# SparkFun_Air_Quality_ENS160.net
KiCad netlist of a schematic drawn in EAGLE
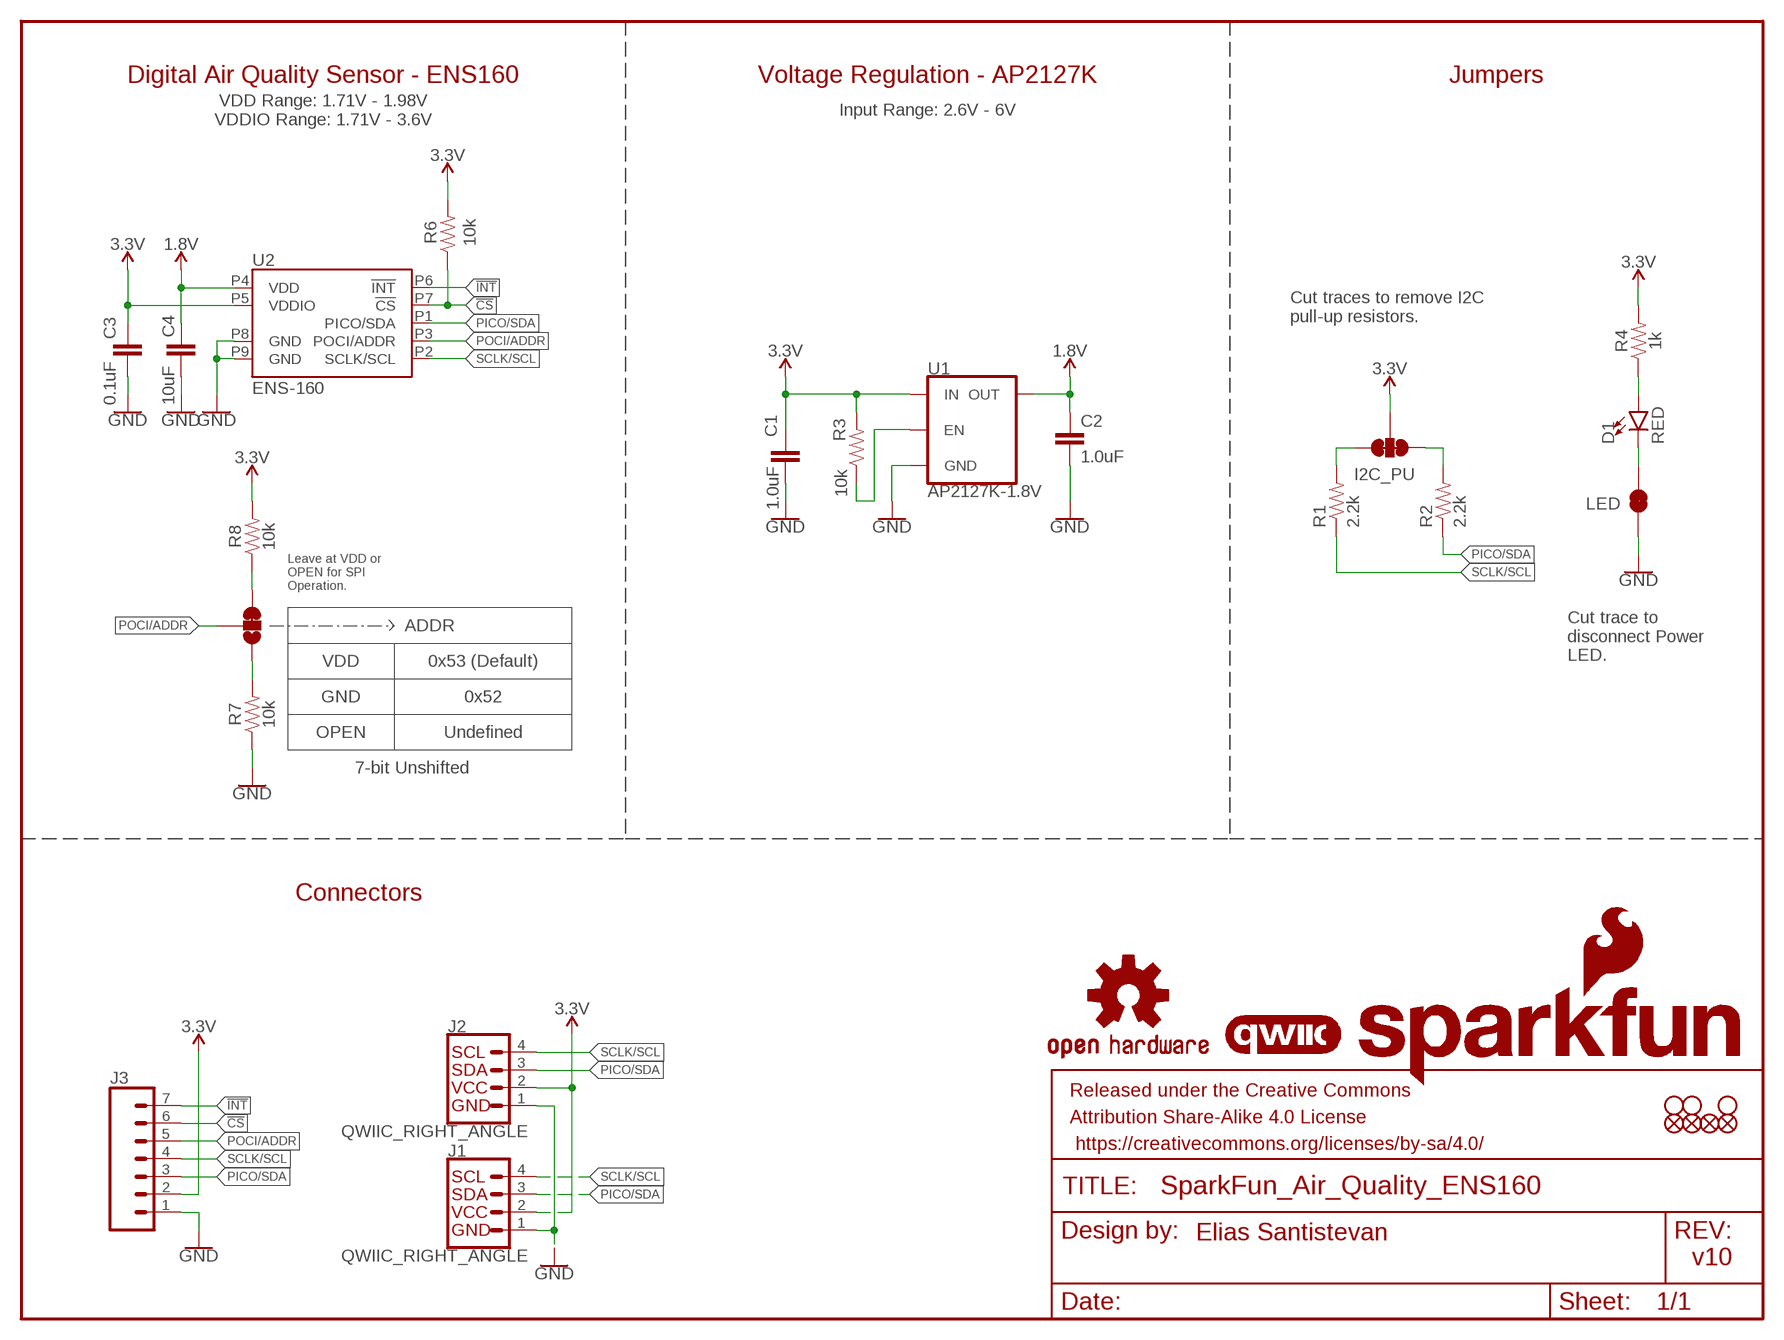
[diagram p0: schematic, sheet 1]

(export (version "E")
  (design (tool "Eeschema 10.0.6"))
  (components
    (comp (ref "ADDR")
      (value "JUMPER-SMT_3_1-NC_TRACE_SILK")
      (footprint "eagle-import:SMT-JUMPER_3_1-NC_TRACE_SILK")
      (libsource (lib "eagle-import") (part "JUMPER-SMT_3_1-NC_TRACE_SILK"))
    )
    (comp (ref "C1")
      (value "1.0uF")
      (footprint "eagle-import:0603")
      (libsource (lib "eagle-import") (part "1.0UF-0603-16V-10%"))
    )
    (comp (ref "C2")
      (value "1.0uF")
      (footprint "eagle-import:0603")
      (libsource (lib "eagle-import") (part "1.0UF-0603-16V-10%"))
    )
    (comp (ref "C3")
      (value "0.1uF")
      (footprint "eagle-import:0603")
      (libsource (lib "eagle-import") (part "0.1UF-0603-25V-(+80/-20%)"))
    )
    (comp (ref "C4")
      (value "10uF")
      (footprint "eagle-import:0603")
      (libsource (lib "eagle-import") (part "10UF-0603-6.3V-20%"))
    )
    (comp (ref "D1")
      (value "RED")
      (footprint "eagle-import:LED-0603")
      (libsource (lib "eagle-import") (part "LED-RED0603"))
    )
    (comp (ref "FD1")
      (value "FIDUCIAL1X2")
      (footprint "eagle-import:FIDUCIAL-1X2")
      (libsource (lib "eagle-import") (part "FIDUCIAL1X2"))
    )
    (comp (ref "FD2")
      (value "FIDUCIAL1X2")
      (footprint "eagle-import:FIDUCIAL-1X2")
      (libsource (lib "eagle-import") (part "FIDUCIAL1X2"))
    )
    (comp (ref "FD3")
      (value "FIDUCIAL1X2")
      (footprint "eagle-import:FIDUCIAL-1X2")
      (libsource (lib "eagle-import") (part "FIDUCIAL1X2"))
    )
    (comp (ref "FD4")
      (value "FIDUCIAL1X2")
      (footprint "eagle-import:FIDUCIAL-1X2")
      (libsource (lib "eagle-import") (part "FIDUCIAL1X2"))
    )
    (comp (ref "FRAME1")
      (value "FRAME-LETTER")
      (footprint "eagle-import:CREATIVE_COMMONS")
      (fields (field (name "DESIGNER") "Elias Santistevan"))
      (libsource (lib "eagle-import") (part "FRAME-LETTER"))
    )
    (comp (ref "I2C_PU")
      (value "S_MODE")
      (footprint "eagle-import:SMT-JUMPER_3_2-NC_TRACE_SILK")
      (libsource (lib "eagle-import") (part "JUMPER-SMT_3_2-NC_TRACE_SILK"))
    )
    (comp (ref "J1")
      (value "QWIIC_RIGHT_ANGLE")
      (footprint "eagle-import:JST04_1MM_RA")
      (libsource (lib "eagle-import") (part "QWIIC_CONNECTORJS-1MM"))
    )
    (comp (ref "J2")
      (value "QWIIC_RIGHT_ANGLE")
      (footprint "eagle-import:JST04_1MM_RA")
      (libsource (lib "eagle-import") (part "QWIIC_CONNECTORJS-1MM"))
    )
    (comp (ref "J3")
      (value "CONN_07NO_SILK")
      (footprint "eagle-import:1X07_NO_SILK")
      (libsource (lib "eagle-import") (part "CONN_07NO_SILK"))
    )
    (comp (ref "LED")
      (value "JUMPER-SMT_2_NC_TRACE_SILK")
      (footprint "eagle-import:SMT-JUMPER_2_NC_TRACE_SILK")
      (libsource (lib "eagle-import") (part "JUMPER-SMT_2_NC_TRACE_SILK"))
    )
    (comp (ref "LOGO2")
      (value "OSHW-LOGOMINI")
      (footprint "eagle-import:OSHW-LOGO-MINI")
      (libsource (lib "eagle-import") (part "OSHW-LOGOMINI"))
    )
    (comp (ref "LOGO3")
      (value "SFE_LOGO_NAME_FLAME.1_INCH")
      (footprint "eagle-import:SFE_LOGO_NAME_FLAME_.1")
      (libsource (lib "eagle-import") (part "SFE_LOGO_NAME_FLAME.1_INCH"))
    )
    (comp (ref "LOGO4")
      (value "QWIIC_LOGO_4MM")
      (footprint "eagle-import:QWIIC_4MM")
      (libsource (lib "eagle-import") (part "QWIIC_LOGO_4MM"))
    )
    (comp (ref "R1")
      (value "2.2k")
      (footprint "eagle-import:0603")
      (libsource (lib "eagle-import") (part "2.2KOHM-0603-1/10W-1%"))
    )
    (comp (ref "R2")
      (value "2.2k")
      (footprint "eagle-import:0603")
      (libsource (lib "eagle-import") (part "2.2KOHM-0603-1/10W-1%"))
    )
    (comp (ref "R3")
      (value "10k")
      (footprint "eagle-import:0603")
      (libsource (lib "eagle-import") (part "10KOHM-0603-1/10W-1%"))
    )
    (comp (ref "R4")
      (value "1k")
      (footprint "eagle-import:0603")
      (libsource (lib "eagle-import") (part "1KOHM-0603-1/10W-1%"))
    )
    (comp (ref "R6")
      (value "10k")
      (footprint "eagle-import:0603")
      (libsource (lib "eagle-import") (part "10KOHM-0603-1/10W-1%"))
    )
    (comp (ref "R7")
      (value "10k")
      (footprint "eagle-import:0603")
      (libsource (lib "eagle-import") (part "10KOHM-0603-1/10W-1%"))
    )
    (comp (ref "R8")
      (value "10k")
      (footprint "eagle-import:0603")
      (libsource (lib "eagle-import") (part "10KOHM-0603-1/10W-1%"))
    )
    (comp (ref "STANDOFF1")
      (value "STAND-OFFTIGHT")
      (footprint "eagle-import:STAND-OFF-TIGHT")
      (libsource (lib "eagle-import") (part "STAND-OFFTIGHT"))
    )
    (comp (ref "STANDOFF2")
      (value "STAND-OFFTIGHT")
      (footprint "eagle-import:STAND-OFF-TIGHT")
      (libsource (lib "eagle-import") (part "STAND-OFFTIGHT"))
    )
    (comp (ref "STANDOFF5")
      (value "STAND-OFFTIGHT")
      (footprint "eagle-import:STAND-OFF-TIGHT")
      (libsource (lib "eagle-import") (part "STAND-OFFTIGHT"))
    )
    (comp (ref "U1")
      (value "AP2127K-1.8V")
      (footprint "eagle-import:SOT23-5")
      (libsource (lib "eagle-import") (part "V_REG_AP2127K-1.8V"))
    )
    (comp (ref "U2")
      (value "ENS-160")
      (footprint "eagle-import:LGA-9")
      (libsource (lib "eagle-import") (part "ENS-160"))
    )
  )
  (nets
    (net (code "1") (name "/~{CS}") (class "Default")
      (node (ref "J3") (pin "6") (pinfunction "6_6") (pintype "passive"))
      (node (ref "R6") (pin "1") (pinfunction "1_1") (pintype "passive"))
      (node (ref "U2") (pin "P7") (pinfunction "~{CS}_P7") (pintype "bidirectional"))
    )
    (net (code "2") (name "/~{INT}") (class "Default")
      (node (ref "J3") (pin "7") (pinfunction "7_7") (pintype "passive"))
      (node (ref "U2") (pin "P6") (pinfunction "~{INT}_P6") (pintype "bidirectional"))
    )
    (net (code "3") (name "1.8V") (class "Default")
      (node (ref "C2") (pin "1") (pinfunction "1_1") (pintype "passive"))
      (node (ref "C4") (pin "1") (pinfunction "1_1") (pintype "passive"))
      (node (ref "U1") (pin "5") (pinfunction "OUT_5") (pintype "passive"))
      (node (ref "U2") (pin "P4") (pinfunction "VDD_P4") (pintype "power_in"))
    )
    (net (code "4") (name "3.3V") (class "Default")
      (node (ref "C1") (pin "1") (pinfunction "1_1") (pintype "passive"))
      (node (ref "C3") (pin "1") (pinfunction "1_1") (pintype "passive"))
      (node (ref "I2C_PU") (pin "2") (pinfunction "2_2") (pintype "passive"))
      (node (ref "J1") (pin "2") (pinfunction "2_2") (pintype "power_in"))
      (node (ref "J2") (pin "2") (pinfunction "2_2") (pintype "power_in"))
      (node (ref "J3") (pin "2") (pinfunction "2_2") (pintype "passive"))
      (node (ref "R3") (pin "2") (pinfunction "2_2") (pintype "passive"))
      (node (ref "R4") (pin "2") (pinfunction "2_2") (pintype "passive"))
      (node (ref "R6") (pin "2") (pinfunction "2_2") (pintype "passive"))
      (node (ref "R8") (pin "2") (pinfunction "2_2") (pintype "passive"))
      (node (ref "U1") (pin "1") (pinfunction "IN_1") (pintype "input"))
      (node (ref "U2") (pin "P5") (pinfunction "VDDIO_P5") (pintype "power_in"))
    )
    (net (code "5") (name "GND") (class "Default")
      (node (ref "C1") (pin "2") (pinfunction "2_2") (pintype "passive"))
      (node (ref "C2") (pin "2") (pinfunction "2_2") (pintype "passive"))
      (node (ref "C3") (pin "2") (pinfunction "2_2") (pintype "passive"))
      (node (ref "C4") (pin "2") (pinfunction "2_2") (pintype "passive"))
      (node (ref "J1") (pin "1") (pinfunction "1_1") (pintype "power_in"))
      (node (ref "J2") (pin "1") (pinfunction "1_1") (pintype "power_in"))
      (node (ref "J3") (pin "1") (pinfunction "1_1") (pintype "passive"))
      (node (ref "LED") (pin "1") (pinfunction "1_1") (pintype "passive"))
      (node (ref "R7") (pin "1") (pinfunction "1_1") (pintype "passive"))
      (node (ref "U1") (pin "2") (pinfunction "GND_2") (pintype "input"))
      (node (ref "U2") (pin "P8") (pinfunction "GND_P8") (pintype "power_in"))
      (node (ref "U2") (pin "P9") (pinfunction "GND_P9") (pintype "power_in"))
    )
    (net (code "6") (name "Net-(ADDR-Pad1)") (class "Default")
      (node (ref "ADDR") (pin "1") (pinfunction "1_1") (pintype "passive"))
      (node (ref "R7") (pin "2") (pinfunction "2_2") (pintype "passive"))
    )
    (net (code "7") (name "Net-(ADDR-Pad3)") (class "Default")
      (node (ref "ADDR") (pin "3") (pinfunction "3_3") (pintype "passive"))
      (node (ref "R8") (pin "1") (pinfunction "1_1") (pintype "passive"))
    )
    (net (code "8") (name "Net-(D1-PadA)") (class "Default")
      (node (ref "D1") (pin "A") (pinfunction "A_A") (pintype "passive"))
      (node (ref "R4") (pin "1") (pinfunction "1_1") (pintype "passive"))
    )
    (net (code "9") (name "Net-(D1-PadC)") (class "Default")
      (node (ref "D1") (pin "C") (pinfunction "C_C") (pintype "passive"))
      (node (ref "LED") (pin "2") (pinfunction "2_2") (pintype "passive"))
    )
    (net (code "10") (name "Net-(I2C_PU-Pad1)") (class "Default")
      (node (ref "I2C_PU") (pin "1") (pinfunction "1_1") (pintype "passive"))
      (node (ref "R1") (pin "2") (pinfunction "2_2") (pintype "passive"))
    )
    (net (code "11") (name "Net-(I2C_PU-Pad3)") (class "Default")
      (node (ref "I2C_PU") (pin "3") (pinfunction "3_3") (pintype "passive"))
      (node (ref "R2") (pin "2") (pinfunction "2_2") (pintype "passive"))
    )
    (net (code "12") (name "Net-(U1-EN)") (class "Default")
      (node (ref "R3") (pin "1") (pinfunction "1_1") (pintype "passive"))
      (node (ref "U1") (pin "3") (pinfunction "EN_3") (pintype "input"))
    )
    (net (code "13") (name "PICO{slash}SDA") (class "Default")
      (node (ref "J1") (pin "3") (pinfunction "3_3") (pintype "passive"))
      (node (ref "J2") (pin "3") (pinfunction "3_3") (pintype "passive"))
      (node (ref "J3") (pin "3") (pinfunction "3_3") (pintype "passive"))
      (node (ref "R2") (pin "1") (pinfunction "1_1") (pintype "passive"))
      (node (ref "U2") (pin "P1") (pinfunction "PICO/SDA_P1") (pintype "bidirectional"))
    )
    (net (code "14") (name "POCI{slash}ADDR") (class "Default")
      (node (ref "ADDR") (pin "2") (pinfunction "2_2") (pintype "passive"))
      (node (ref "J3") (pin "5") (pinfunction "5_5") (pintype "passive"))
      (node (ref "U2") (pin "P3") (pinfunction "POCI/ADDR_P3") (pintype "bidirectional"))
    )
    (net (code "15") (name "SCLK{slash}SCL") (class "Default")
      (node (ref "J1") (pin "4") (pinfunction "4_4") (pintype "passive"))
      (node (ref "J2") (pin "4") (pinfunction "4_4") (pintype "passive"))
      (node (ref "J3") (pin "4") (pinfunction "4_4") (pintype "passive"))
      (node (ref "R1") (pin "1") (pinfunction "1_1") (pintype "passive"))
      (node (ref "U2") (pin "P2") (pinfunction "SCLK/SCL_P2") (pintype "bidirectional"))
    )
  )
)
